# Workshop_000.net
KiCad netlist of a schematic drawn in EAGLE
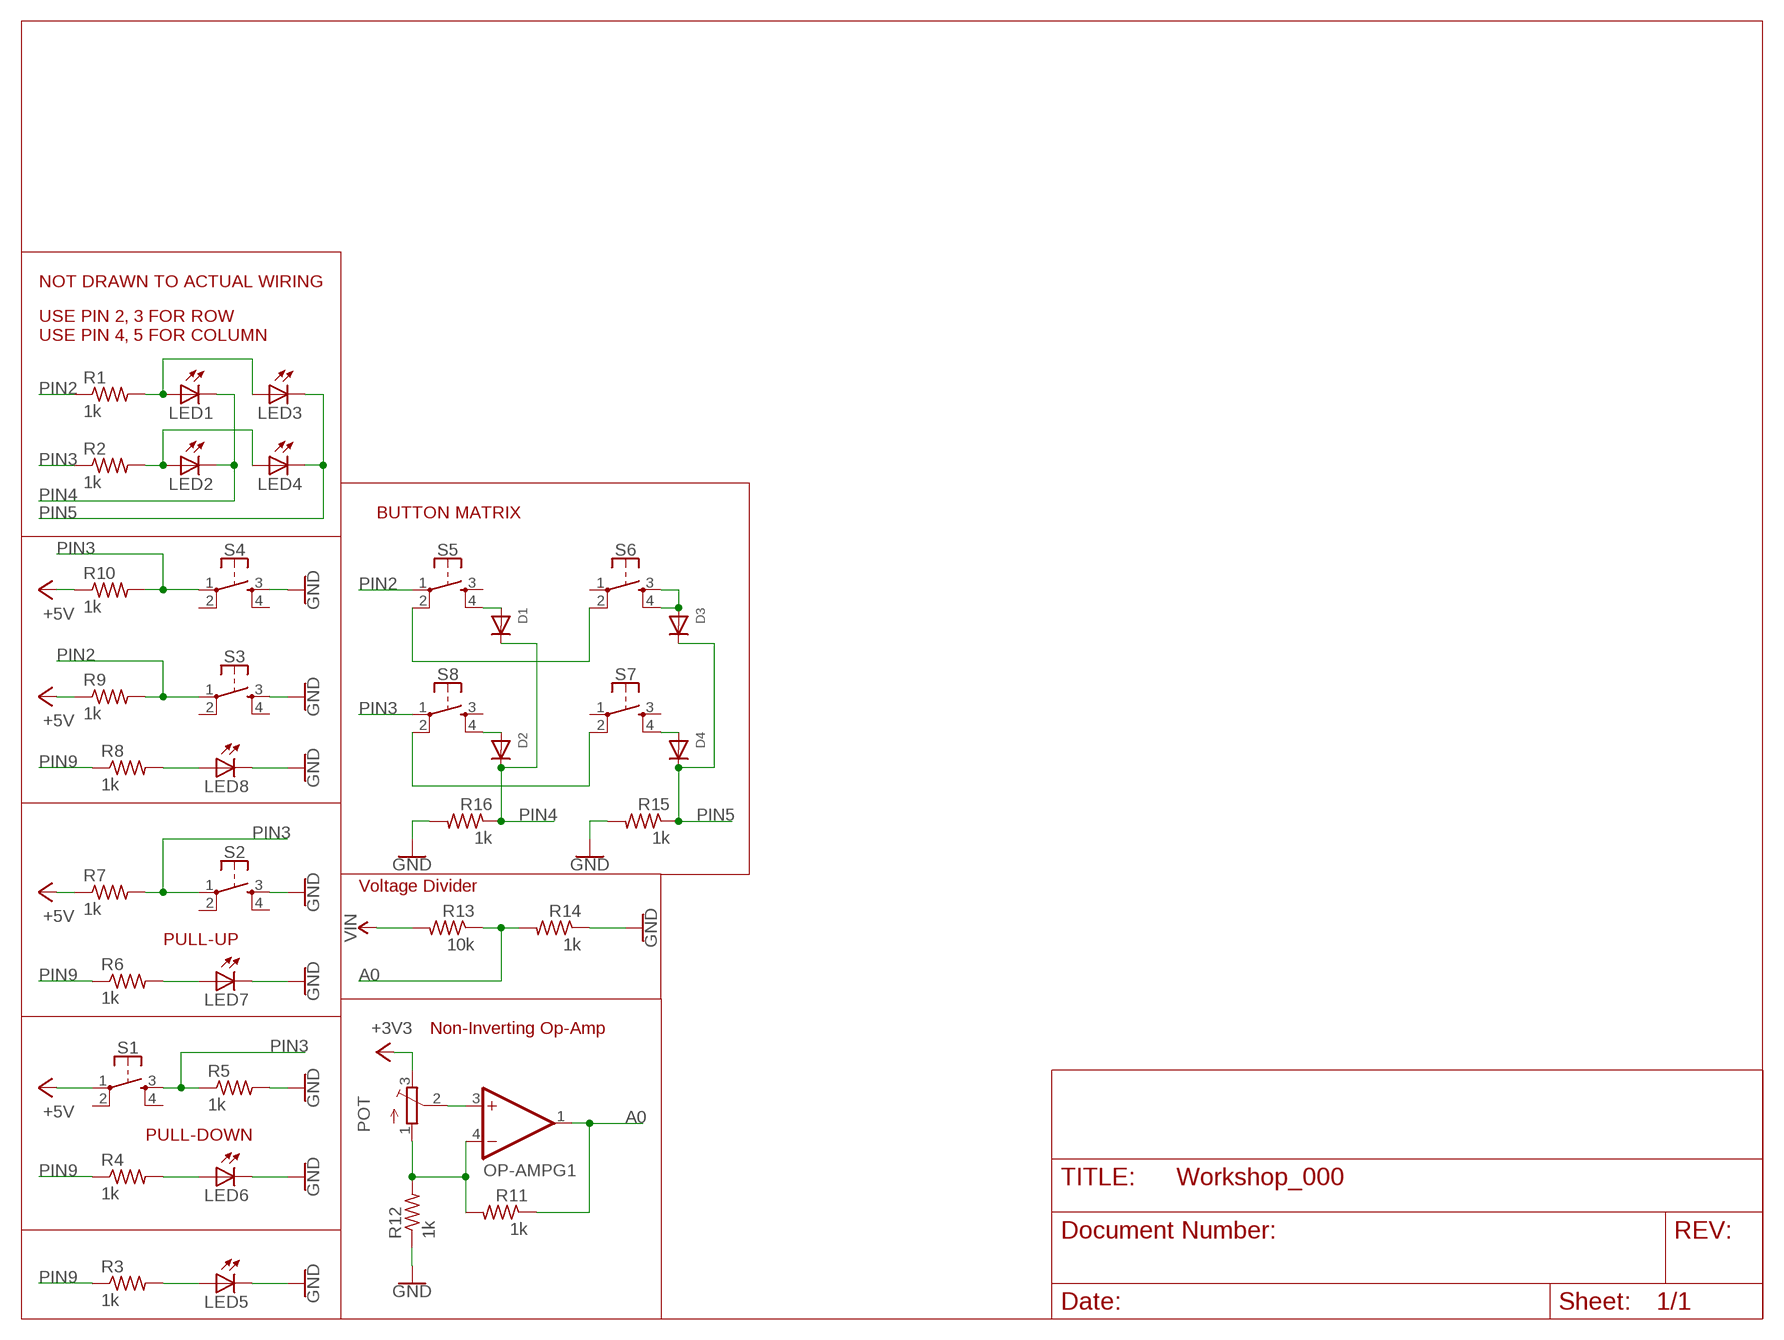
[diagram p0: schematic, sheet 1]

(export (version "E")
  (design (tool "Eeschema 10.0.6"))
  (components
    (comp (ref "D1")
      (value "DIODEDO-1N4148")
      (footprint "eagle-import:DO-1N4148")
      (libsource (lib "eagle-import") (part "DIODEDO-1N4148"))
    )
    (comp (ref "D2")
      (value "DIODEDO-1N4148")
      (footprint "eagle-import:DO-1N4148")
      (libsource (lib "eagle-import") (part "DIODEDO-1N4148"))
    )
    (comp (ref "D3")
      (value "DIODEDO-1N4148")
      (footprint "eagle-import:DO-1N4148")
      (libsource (lib "eagle-import") (part "DIODEDO-1N4148"))
    )
    (comp (ref "D4")
      (value "DIODEDO-1N4148")
      (footprint "eagle-import:DO-1N4148")
      (libsource (lib "eagle-import") (part "DIODEDO-1N4148"))
    )
    (comp (ref "LED1")
      (value "LED5MM")
      (footprint "eagle-import:LED5MM")
      (libsource (lib "eagle-import") (part "LED5MM"))
    )
    (comp (ref "LED2")
      (value "LED5MM")
      (footprint "eagle-import:LED5MM")
      (libsource (lib "eagle-import") (part "LED5MM"))
    )
    (comp (ref "LED3")
      (value "LED5MM")
      (footprint "eagle-import:LED5MM")
      (libsource (lib "eagle-import") (part "LED5MM"))
    )
    (comp (ref "LED4")
      (value "LED5MM")
      (footprint "eagle-import:LED5MM")
      (libsource (lib "eagle-import") (part "LED5MM"))
    )
    (comp (ref "LED5")
      (value "LED5MM")
      (footprint "eagle-import:LED5MM")
      (libsource (lib "eagle-import") (part "LED5MM"))
    )
    (comp (ref "LED6")
      (value "LED5MM")
      (footprint "eagle-import:LED5MM")
      (libsource (lib "eagle-import") (part "LED5MM"))
    )
    (comp (ref "LED7")
      (value "LED5MM")
      (footprint "eagle-import:LED5MM")
      (libsource (lib "eagle-import") (part "LED5MM"))
    )
    (comp (ref "LED8")
      (value "LED5MM")
      (footprint "eagle-import:LED5MM")
      (libsource (lib "eagle-import") (part "LED5MM"))
    )
    (comp (ref "OP-AMP")
      (value "MCP6021T-E/OT")
      (footprint "eagle-import:SOT23-5")
      (libsource (lib "eagle-import") (part "MCP6021T-E/OT"))
    )
    (comp (ref "POT")
      (value "TRIMPOT3386")
      (footprint "eagle-import:TRIM-3386")
      (libsource (lib "eagle-import") (part "TRIMPOT3386"))
    )
    (comp (ref "R1")
      (value "1k")
      (footprint "eagle-import:M0805")
      (libsource (lib "eagle-import") (part "R-US_M0805"))
    )
    (comp (ref "R2")
      (value "1k")
      (footprint "eagle-import:M0805")
      (libsource (lib "eagle-import") (part "R-US_M0805"))
    )
    (comp (ref "R3")
      (value "1k")
      (footprint "eagle-import:M0805")
      (libsource (lib "eagle-import") (part "R-US_M0805"))
    )
    (comp (ref "R4")
      (value "1k")
      (footprint "eagle-import:M0805")
      (libsource (lib "eagle-import") (part "R-US_M0805"))
    )
    (comp (ref "R5")
      (value "1k")
      (footprint "eagle-import:M0805")
      (libsource (lib "eagle-import") (part "R-US_M0805"))
    )
    (comp (ref "R6")
      (value "1k")
      (footprint "eagle-import:M0805")
      (libsource (lib "eagle-import") (part "R-US_M0805"))
    )
    (comp (ref "R7")
      (value "1k")
      (footprint "eagle-import:M0805")
      (libsource (lib "eagle-import") (part "R-US_M0805"))
    )
    (comp (ref "R8")
      (value "1k")
      (footprint "eagle-import:M0805")
      (libsource (lib "eagle-import") (part "R-US_M0805"))
    )
    (comp (ref "R9")
      (value "1k")
      (footprint "eagle-import:M0805")
      (libsource (lib "eagle-import") (part "R-US_M0805"))
    )
    (comp (ref "R10")
      (value "1k")
      (footprint "eagle-import:M0805")
      (libsource (lib "eagle-import") (part "R-US_M0805"))
    )
    (comp (ref "R11")
      (value "1k")
      (footprint "eagle-import:R0805")
      (libsource (lib "eagle-import") (part "R-US_R0805"))
    )
    (comp (ref "R12")
      (value "1k")
      (footprint "eagle-import:R0805")
      (libsource (lib "eagle-import") (part "R-US_R0805"))
    )
    (comp (ref "R13")
      (value "10k")
      (footprint "eagle-import:R0805")
      (libsource (lib "eagle-import") (part "R-US_R0805"))
    )
    (comp (ref "R14")
      (value "1k")
      (footprint "eagle-import:R0805")
      (libsource (lib "eagle-import") (part "R-US_R0805"))
    )
    (comp (ref "R15")
      (value "1k")
      (footprint "eagle-import:R0805")
      (libsource (lib "eagle-import") (part "R-US_R0805"))
    )
    (comp (ref "R16")
      (value "1k")
      (footprint "eagle-import:R0805")
      (libsource (lib "eagle-import") (part "R-US_R0805"))
    )
    (comp (ref "S1")
      (value "MOMENTARY-SWITCH-SPST-2-SMD-5.2MM")
      (footprint "eagle-import:TACTILE_SWITCH_SMD_5.2MM")
      (libsource (lib "eagle-import") (part "MOMENTARY-SWITCH-SPST-2-SMD-5.2MM"))
    )
    (comp (ref "S2")
      (value "MOMENTARY-SWITCH-SPST-2-SMD-5.2MM")
      (footprint "eagle-import:TACTILE_SWITCH_SMD_5.2MM")
      (libsource (lib "eagle-import") (part "MOMENTARY-SWITCH-SPST-2-SMD-5.2MM"))
    )
    (comp (ref "S3")
      (value "MOMENTARY-SWITCH-SPST-2-SMD-5.2MM")
      (footprint "eagle-import:TACTILE_SWITCH_SMD_5.2MM")
      (libsource (lib "eagle-import") (part "MOMENTARY-SWITCH-SPST-2-SMD-5.2MM"))
    )
    (comp (ref "S4")
      (value "MOMENTARY-SWITCH-SPST-2-SMD-5.2MM")
      (footprint "eagle-import:TACTILE_SWITCH_SMD_5.2MM")
      (libsource (lib "eagle-import") (part "MOMENTARY-SWITCH-SPST-2-SMD-5.2MM"))
    )
    (comp (ref "S5")
      (value "MOMENTARY-SWITCH-SPST-2-SMD-5.2MM")
      (footprint "eagle-import:TACTILE_SWITCH_SMD_5.2MM")
      (libsource (lib "eagle-import") (part "MOMENTARY-SWITCH-SPST-2-SMD-5.2MM"))
    )
    (comp (ref "S6")
      (value "MOMENTARY-SWITCH-SPST-2-SMD-5.2MM")
      (footprint "eagle-import:TACTILE_SWITCH_SMD_5.2MM")
      (libsource (lib "eagle-import") (part "MOMENTARY-SWITCH-SPST-2-SMD-5.2MM"))
    )
    (comp (ref "S7")
      (value "MOMENTARY-SWITCH-SPST-2-SMD-5.2MM")
      (footprint "eagle-import:TACTILE_SWITCH_SMD_5.2MM")
      (libsource (lib "eagle-import") (part "MOMENTARY-SWITCH-SPST-2-SMD-5.2MM"))
    )
    (comp (ref "S8")
      (value "MOMENTARY-SWITCH-SPST-2-SMD-5.2MM")
      (footprint "eagle-import:TACTILE_SWITCH_SMD_5.2MM")
      (libsource (lib "eagle-import") (part "MOMENTARY-SWITCH-SPST-2-SMD-5.2MM"))
    )
  )
  (nets
    (net (code "1") (name "+3V3") (class "Default")
      (node (ref "POT") (pin "3") (pinfunction "E_3") (pintype "passive"))
    )
    (net (code "2") (name "+5V") (class "Default")
      (node (ref "R10") (pin "1") (pinfunction "1_1") (pintype "passive"))
      (node (ref "R7") (pin "1") (pinfunction "1_1") (pintype "passive"))
      (node (ref "R9") (pin "1") (pinfunction "1_1") (pintype "passive"))
      (node (ref "S1") (pin "1") (pinfunction "1_1") (pintype "passive"))
    )
    (net (code "3") (name "/A0") (class "Default")
      (node (ref "OP-AMP") (pin "1") (pinfunction "OUT_1") (pintype "output"))
      (node (ref "R11") (pin "1") (pinfunction "1_1") (pintype "passive"))
      (node (ref "R13") (pin "1") (pinfunction "1_1") (pintype "passive"))
      (node (ref "R14") (pin "2") (pinfunction "2_2") (pintype "passive"))
    )
    (net (code "4") (name "/PIN2") (class "Default")
      (node (ref "R1") (pin "1") (pinfunction "1_1") (pintype "passive"))
      (node (ref "R9") (pin "2") (pinfunction "2_2") (pintype "passive"))
      (node (ref "S3") (pin "1") (pinfunction "1_1") (pintype "passive"))
      (node (ref "S5") (pin "1") (pinfunction "1_1") (pintype "passive"))
    )
    (net (code "5") (name "/PIN3") (class "Default")
      (node (ref "R10") (pin "2") (pinfunction "2_2") (pintype "passive"))
      (node (ref "R2") (pin "1") (pinfunction "1_1") (pintype "passive"))
      (node (ref "R5") (pin "1") (pinfunction "1_1") (pintype "passive"))
      (node (ref "R7") (pin "2") (pinfunction "2_2") (pintype "passive"))
      (node (ref "S1") (pin "3") (pinfunction "3_3") (pintype "passive"))
      (node (ref "S2") (pin "1") (pinfunction "1_1") (pintype "passive"))
      (node (ref "S4") (pin "1") (pinfunction "1_1") (pintype "passive"))
      (node (ref "S8") (pin "1") (pinfunction "1_1") (pintype "passive"))
    )
    (net (code "6") (name "/PIN4") (class "Default")
      (node (ref "D1") (pin "C") (pinfunction "C_C") (pintype "passive"))
      (node (ref "D2") (pin "C") (pinfunction "C_C") (pintype "passive"))
      (node (ref "LED1") (pin "K") (pinfunction "C_K") (pintype "passive"))
      (node (ref "LED2") (pin "K") (pinfunction "C_K") (pintype "passive"))
      (node (ref "R16") (pin "1") (pinfunction "1_1") (pintype "passive"))
    )
    (net (code "7") (name "/PIN5") (class "Default")
      (node (ref "D3") (pin "C") (pinfunction "C_C") (pintype "passive"))
      (node (ref "D4") (pin "C") (pinfunction "C_C") (pintype "passive"))
      (node (ref "LED3") (pin "K") (pinfunction "C_K") (pintype "passive"))
      (node (ref "LED4") (pin "K") (pinfunction "C_K") (pintype "passive"))
      (node (ref "R15") (pin "1") (pinfunction "1_1") (pintype "passive"))
    )
    (net (code "8") (name "/PIN9") (class "Default")
      (node (ref "R3") (pin "1") (pinfunction "1_1") (pintype "passive"))
      (node (ref "R4") (pin "1") (pinfunction "1_1") (pintype "passive"))
      (node (ref "R6") (pin "1") (pinfunction "1_1") (pintype "passive"))
      (node (ref "R8") (pin "1") (pinfunction "1_1") (pintype "passive"))
    )
    (net (code "9") (name "GND") (class "Default")
      (node (ref "LED5") (pin "K") (pinfunction "C_K") (pintype "passive"))
      (node (ref "LED6") (pin "K") (pinfunction "C_K") (pintype "passive"))
      (node (ref "LED7") (pin "K") (pinfunction "C_K") (pintype "passive"))
      (node (ref "LED8") (pin "K") (pinfunction "C_K") (pintype "passive"))
      (node (ref "R12") (pin "1") (pinfunction "1_1") (pintype "passive"))
      (node (ref "R14") (pin "1") (pinfunction "1_1") (pintype "passive"))
      (node (ref "R15") (pin "2") (pinfunction "2_2") (pintype "passive"))
      (node (ref "R16") (pin "2") (pinfunction "2_2") (pintype "passive"))
      (node (ref "R5") (pin "2") (pinfunction "2_2") (pintype "passive"))
      (node (ref "S2") (pin "3") (pinfunction "3_3") (pintype "passive"))
      (node (ref "S3") (pin "3") (pinfunction "3_3") (pintype "passive"))
      (node (ref "S4") (pin "3") (pinfunction "3_3") (pintype "passive"))
    )
    (net (code "10") (name "Net-(D1-PadA)") (class "Default")
      (node (ref "D1") (pin "A") (pinfunction "A_A") (pintype "passive"))
      (node (ref "S5") (pin "4") (pinfunction "4_4") (pintype "passive"))
    )
    (net (code "11") (name "Net-(D2-PadA)") (class "Default")
      (node (ref "D2") (pin "A") (pinfunction "A_A") (pintype "passive"))
      (node (ref "S8") (pin "4") (pinfunction "4_4") (pintype "passive"))
    )
    (net (code "12") (name "Net-(D3-PadA)") (class "Default")
      (node (ref "D3") (pin "A") (pinfunction "A_A") (pintype "passive"))
      (node (ref "S6") (pin "3") (pinfunction "3_3") (pintype "passive"))
      (node (ref "S6") (pin "4") (pinfunction "4_4") (pintype "passive"))
    )
    (net (code "13") (name "Net-(D4-PadA)") (class "Default")
      (node (ref "D4") (pin "A") (pinfunction "A_A") (pintype "passive"))
      (node (ref "S7") (pin "4") (pinfunction "4_4") (pintype "passive"))
    )
    (net (code "14") (name "Net-(LED1-PadA)") (class "Default")
      (node (ref "LED1") (pin "A") (pinfunction "A_A") (pintype "passive"))
      (node (ref "LED3") (pin "A") (pinfunction "A_A") (pintype "passive"))
      (node (ref "R1") (pin "2") (pinfunction "2_2") (pintype "passive"))
    )
    (net (code "15") (name "Net-(LED2-PadA)") (class "Default")
      (node (ref "LED2") (pin "A") (pinfunction "A_A") (pintype "passive"))
      (node (ref "LED4") (pin "A") (pinfunction "A_A") (pintype "passive"))
      (node (ref "R2") (pin "2") (pinfunction "2_2") (pintype "passive"))
    )
    (net (code "16") (name "Net-(LED5-PadA)") (class "Default")
      (node (ref "LED5") (pin "A") (pinfunction "A_A") (pintype "passive"))
      (node (ref "R3") (pin "2") (pinfunction "2_2") (pintype "passive"))
    )
    (net (code "17") (name "Net-(LED6-PadA)") (class "Default")
      (node (ref "LED6") (pin "A") (pinfunction "A_A") (pintype "passive"))
      (node (ref "R4") (pin "2") (pinfunction "2_2") (pintype "passive"))
    )
    (net (code "18") (name "Net-(LED7-PadA)") (class "Default")
      (node (ref "LED7") (pin "A") (pinfunction "A_A") (pintype "passive"))
      (node (ref "R6") (pin "2") (pinfunction "2_2") (pintype "passive"))
    )
    (net (code "19") (name "Net-(LED8-PadA)") (class "Default")
      (node (ref "LED8") (pin "A") (pinfunction "A_A") (pintype "passive"))
      (node (ref "R8") (pin "2") (pinfunction "2_2") (pintype "passive"))
    )
    (net (code "20") (name "Net-(OP-AMPA-+IN)") (class "Default")
      (node (ref "OP-AMP") (pin "3") (pinfunction "+IN_3") (pintype "input"))
      (node (ref "POT") (pin "2") (pinfunction "S_2") (pintype "passive"))
    )
    (net (code "21") (name "Net-(OP-AMPA--IN)") (class "Default")
      (node (ref "OP-AMP") (pin "4") (pinfunction "-IN_4") (pintype "input"))
      (node (ref "POT") (pin "1") (pinfunction "A_1") (pintype "passive"))
      (node (ref "R11") (pin "2") (pinfunction "2_2") (pintype "passive"))
      (node (ref "R12") (pin "2") (pinfunction "2_2") (pintype "passive"))
    )
    (net (code "22") (name "Net-(S5-Pad2)") (class "Default")
      (node (ref "S5") (pin "2") (pinfunction "2_2") (pintype "passive"))
      (node (ref "S6") (pin "2") (pinfunction "2_2") (pintype "passive"))
    )
    (net (code "23") (name "Net-(S7-Pad2)") (class "Default")
      (node (ref "S7") (pin "2") (pinfunction "2_2") (pintype "passive"))
      (node (ref "S8") (pin "2") (pinfunction "2_2") (pintype "passive"))
    )
    (net (code "24") (name "VIN") (class "Default")
      (node (ref "R13") (pin "2") (pinfunction "2_2") (pintype "passive"))
    )
    (net (code "25") (name "unconnected-(S1-Pad2)") (class "Default")
      (node (ref "S1") (pin "2") (pinfunction "2_2") (pintype "passive"))
    )
    (net (code "26") (name "unconnected-(S1-Pad4)") (class "Default")
      (node (ref "S1") (pin "4") (pinfunction "4_4") (pintype "passive"))
    )
    (net (code "27") (name "unconnected-(S2-Pad2)") (class "Default")
      (node (ref "S2") (pin "2") (pinfunction "2_2") (pintype "passive"))
    )
    (net (code "28") (name "unconnected-(S2-Pad4)") (class "Default")
      (node (ref "S2") (pin "4") (pinfunction "4_4") (pintype "passive"))
    )
    (net (code "29") (name "unconnected-(S3-Pad2)") (class "Default")
      (node (ref "S3") (pin "2") (pinfunction "2_2") (pintype "passive"))
    )
    (net (code "30") (name "unconnected-(S3-Pad4)") (class "Default")
      (node (ref "S3") (pin "4") (pinfunction "4_4") (pintype "passive"))
    )
    (net (code "31") (name "unconnected-(S4-Pad2)") (class "Default")
      (node (ref "S4") (pin "2") (pinfunction "2_2") (pintype "passive"))
    )
    (net (code "32") (name "unconnected-(S4-Pad4)") (class "Default")
      (node (ref "S4") (pin "4") (pinfunction "4_4") (pintype "passive"))
    )
    (net (code "33") (name "unconnected-(S5-Pad3)") (class "Default")
      (node (ref "S5") (pin "3") (pinfunction "3_3") (pintype "passive"))
    )
    (net (code "34") (name "unconnected-(S6-Pad1)") (class "Default")
      (node (ref "S6") (pin "1") (pinfunction "1_1") (pintype "passive"))
    )
    (net (code "35") (name "unconnected-(S7-Pad1)") (class "Default")
      (node (ref "S7") (pin "1") (pinfunction "1_1") (pintype "passive"))
    )
    (net (code "36") (name "unconnected-(S7-Pad3)") (class "Default")
      (node (ref "S7") (pin "3") (pinfunction "3_3") (pintype "passive"))
    )
    (net (code "37") (name "unconnected-(S8-Pad3)") (class "Default")
      (node (ref "S8") (pin "3") (pinfunction "3_3") (pintype "passive"))
    )
  )
)
